# 20V_Supply.net
KiCad netlist of a schematic drawn in Altium Designer
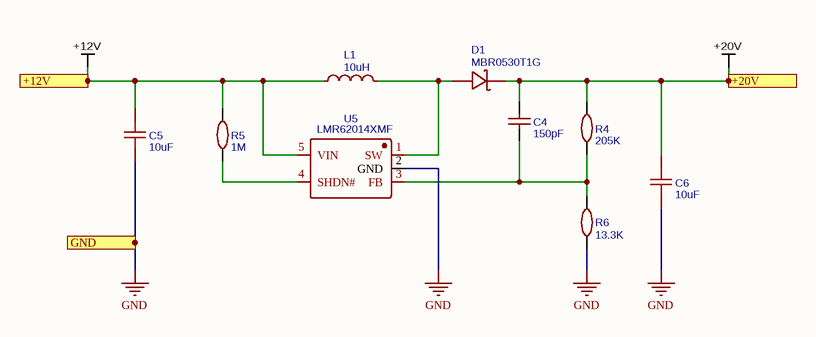
[diagram p0: 20V Supply.SchDoc]

(export (version "E")
  (design (tool "Eeschema 10.0.6"))
  (components
    (comp (ref "C4")
      (value "150pF")
      (footprint "C0805")
      (fields
        (field (name "MANUFACTURER") "YAGEO")
        (field (name "MANUFACTURE PART NUMBER") "CC0805JRNPO9BN151")
      )
      (libsource (lib "altium-import") (part "root_1_150pF_"))
    )
    (comp (ref "C5")
      (value "10uF")
      (footprint "C0805")
      (fields
        (field (name "MANUFACTURER") "SAMSUNG")
        (field (name "MANUFACTURE PART NUMBER") "CL21B106KOQNNNE")
      )
      (libsource (lib "altium-import") (part "root_1_10uF_"))
    )
    (comp (ref "C6")
      (value "10uF")
      (footprint "C0805")
      (fields
        (field (name "MANUFACTURER") "SAMSUNG")
        (field (name "MANUFACTURE PART NUMBER") "CL21B106KOQNNNE")
      )
      (libsource (lib "altium-import") (part "root_1_10uF_"))
    )
    (comp (ref "D1")
      (value "MBR0530T1G")
      (footprint "SOD-123_L2.8-W1.8-LS3.7-RD")
      (fields (field (name "MANUFACTURER") "ON"))
      (libsource (lib "altium-import") (part "root_2_MBR0530T1G_"))
    )
    (comp (ref "L1")
      (value "10uH")
      (footprint "IND-SMD_L6.0-W6.0")
      (fields
        (field (name "MANUFACTURER") "TDK")
        (field (name "MANUFACTURE PART NUMBER") "VLS6045EX-100M")
        (field (name "CONTRIBUTOR") "LCSC")
      )
      (libsource (lib "altium-import") (part "root_0_10uH_"))
    )
    (comp (ref "R4")
      (value "205K")
      (footprint "R0603")
      (fields
        (field (name "MANUFACTURER") "UniOhm")
        (field (name "MANUFACTURE PART NUMBER") "0603WAF2053T5E")
      )
      (libsource (lib "altium-import") (part "root_1_205K_"))
    )
    (comp (ref "R5")
      (value "1M")
      (footprint "R0603")
      (fields
        (field (name "MANUFACTURER") "UniOhm")
        (field (name "MANUFACTURE PART NUMBER") "0603WAF1004T5E")
      )
      (libsource (lib "altium-import") (part "root_1_1M_"))
    )
    (comp (ref "R6")
      (value "13.3K")
      (footprint "R0603")
      (fields
        (field (name "MANUFACTURER") "UniOhm")
        (field (name "MANUFACTURE PART NUMBER") "0603WAF1332T5E")
      )
      (libsource (lib "altium-import") (part "root_1_13.3K_"))
    )
    (comp (ref "U5")
      (value "LMR62014XMF")
      (footprint "SOT-23-5_L3.0-W1.7-P0.95-LS2.8-BR")
      (fields (field (name "MANUFACTURER") "TI"))
      (libsource (lib "altium-import") (part "root_0_LMR62014XMF_"))
    )
  )
  (nets
    (net (code "1") (name "+12V") (class "Default")
      (node (ref "C5") (pin "2") (pinfunction "2_2") (pintype "passive"))
      (node (ref "L1") (pin "1") (pinfunction "1_1") (pintype "passive"))
      (node (ref "R5") (pin "2") (pinfunction "2_2") (pintype "passive"))
      (node (ref "U5") (pin "5") (pinfunction "VIN_5") (pintype "passive"))
    )
    (net (code "2") (name "+20V") (class "Default")
      (node (ref "C4") (pin "2") (pinfunction "2_2") (pintype "passive"))
      (node (ref "C6") (pin "2") (pinfunction "2_2") (pintype "passive"))
      (node (ref "D1") (pin "1") (pinfunction "C_1") (pintype "passive"))
      (node (ref "R4") (pin "2") (pinfunction "2_2") (pintype "passive"))
    )
    (net (code "3") (name "GND") (class "Default")
      (node (ref "C5") (pin "1") (pinfunction "1_1") (pintype "passive"))
      (node (ref "C6") (pin "1") (pinfunction "1_1") (pintype "passive"))
      (node (ref "R6") (pin "1") (pinfunction "1_1") (pintype "passive"))
      (node (ref "U5") (pin "2") (pinfunction "GND_2") (pintype "passive"))
    )
    (net (code "4") (name "Net-(D1-A)") (class "Default")
      (node (ref "D1") (pin "2") (pinfunction "A_2") (pintype "passive"))
      (node (ref "L1") (pin "2") (pinfunction "2_2") (pintype "passive"))
      (node (ref "U5") (pin "1") (pinfunction "SW_1") (pintype "passive"))
    )
    (net (code "5") (name "Net-(U5-FB)") (class "Default")
      (node (ref "C4") (pin "1") (pinfunction "1_1") (pintype "passive"))
      (node (ref "R4") (pin "1") (pinfunction "1_1") (pintype "passive"))
      (node (ref "R6") (pin "2") (pinfunction "2_2") (pintype "passive"))
      (node (ref "U5") (pin "3") (pinfunction "FB_3") (pintype "passive"))
    )
    (net (code "6") (name "Net-(U5-SHDN#)") (class "Default")
      (node (ref "R5") (pin "1") (pinfunction "1_1") (pintype "passive"))
      (node (ref "U5") (pin "4") (pinfunction "SHDN#_4") (pintype "passive"))
    )
  )
)
